# Ch7and8.net
KiCad netlist of a schematic drawn in Altium Designer
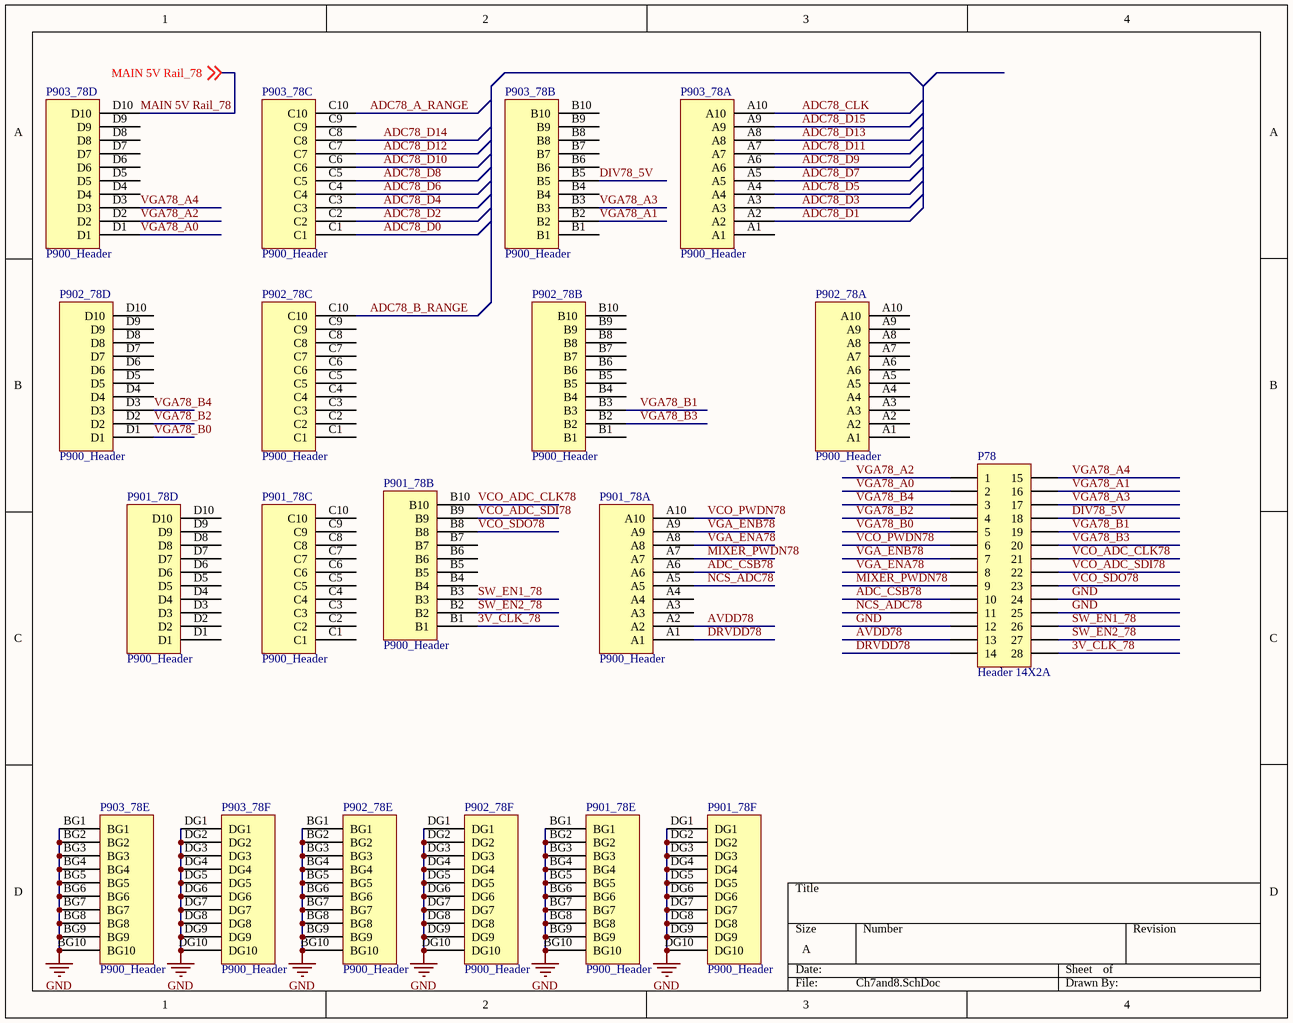
[diagram p0: Ch7and8.SchDoc]

(export (version "E")
  (design (tool "Eeschema 10.0.6"))
  (components
    (comp (ref "P78")
      (value "Header 14X2A")
      (footprint "HDR2X14_CEN")
      (description "Header, 14-Pin, Dual row")
      (fields (field (name "PUBLISHER") "Altium Limited"))
      (libsource (lib "Miscellaneous Connectors") (part "Header 14X2A"))
    )
    (comp (ref "P901_78")
      (value "P900_Header")
      (footprint "P900_header")
      (libsource (lib "") (part "P900_Header_1"))
    )
    (comp (ref "P902_78")
      (value "P900_Header")
      (footprint "P900_header")
      (libsource (lib "MQP_lib") (part "P900_Header"))
    )
    (comp (ref "P903_78")
      (value "P900_Header")
      (footprint "P900_header")
      (libsource (lib "") (part "P900_Header_1"))
    )
  )
  (nets
    (net (code "1") (name "/3V_CLK_78") (class "Default")
      (node (ref "P78") (pin "28") (pinfunction "28_28") (pintype "passive"))
      (node (ref "P901_78") (pin "B1") (pinfunction "B1_B1") (pintype "passive"))
    )
    (net (code "2") (name "/ADC78_A_RANGE") (class "Default")
      (node (ref "P903_78") (pin "C10") (pinfunction "C10_C10") (pintype "passive"))
    )
    (net (code "3") (name "/ADC78_B_RANGE") (class "Default")
      (node (ref "P902_78") (pin "C10") (pinfunction "C10_C10") (pintype "passive"))
    )
    (net (code "4") (name "/ADC78_CLK") (class "Default")
      (node (ref "P903_78") (pin "A10") (pinfunction "A10_A10") (pintype "passive"))
    )
    (net (code "5") (name "/ADC78_D0") (class "Default")
      (node (ref "P903_78") (pin "C1") (pinfunction "C1_C1") (pintype "passive"))
    )
    (net (code "6") (name "/ADC78_D1") (class "Default")
      (node (ref "P903_78") (pin "A2") (pinfunction "A2_A2") (pintype "passive"))
    )
    (net (code "7") (name "/ADC78_D2") (class "Default")
      (node (ref "P903_78") (pin "C2") (pinfunction "C2_C2") (pintype "passive"))
    )
    (net (code "8") (name "/ADC78_D3") (class "Default")
      (node (ref "P903_78") (pin "A3") (pinfunction "A3_A3") (pintype "passive"))
    )
    (net (code "9") (name "/ADC78_D4") (class "Default")
      (node (ref "P903_78") (pin "C3") (pinfunction "C3_C3") (pintype "passive"))
    )
    (net (code "10") (name "/ADC78_D5") (class "Default")
      (node (ref "P903_78") (pin "A4") (pinfunction "A4_A4") (pintype "passive"))
    )
    (net (code "11") (name "/ADC78_D6") (class "Default")
      (node (ref "P903_78") (pin "C4") (pinfunction "C4_C4") (pintype "passive"))
    )
    (net (code "12") (name "/ADC78_D7") (class "Default")
      (node (ref "P903_78") (pin "A5") (pinfunction "A5_A5") (pintype "passive"))
    )
    (net (code "13") (name "/ADC78_D8") (class "Default")
      (node (ref "P903_78") (pin "C5") (pinfunction "C5_C5") (pintype "passive"))
    )
    (net (code "14") (name "/ADC78_D9") (class "Default")
      (node (ref "P903_78") (pin "A6") (pinfunction "A6_A6") (pintype "passive"))
    )
    (net (code "15") (name "/ADC78_D10") (class "Default")
      (node (ref "P903_78") (pin "C6") (pinfunction "C6_C6") (pintype "passive"))
    )
    (net (code "16") (name "/ADC78_D11") (class "Default")
      (node (ref "P903_78") (pin "A7") (pinfunction "A7_A7") (pintype "passive"))
    )
    (net (code "17") (name "/ADC78_D12") (class "Default")
      (node (ref "P903_78") (pin "C7") (pinfunction "C7_C7") (pintype "passive"))
    )
    (net (code "18") (name "/ADC78_D13") (class "Default")
      (node (ref "P903_78") (pin "A8") (pinfunction "A8_A8") (pintype "passive"))
    )
    (net (code "19") (name "/ADC78_D14") (class "Default")
      (node (ref "P903_78") (pin "C8") (pinfunction "C8_C8") (pintype "passive"))
    )
    (net (code "20") (name "/ADC78_D15") (class "Default")
      (node (ref "P903_78") (pin "A9") (pinfunction "A9_A9") (pintype "passive"))
    )
    (net (code "21") (name "/ADC_CSB78") (class "Default")
      (node (ref "P78") (pin "10") (pinfunction "10_10") (pintype "passive"))
      (node (ref "P901_78") (pin "A6") (pinfunction "A6_A6") (pintype "passive"))
    )
    (net (code "22") (name "/AVDD78") (class "Default")
      (node (ref "P78") (pin "13") (pinfunction "13_13") (pintype "passive"))
      (node (ref "P901_78") (pin "A2") (pinfunction "A2_A2") (pintype "passive"))
    )
    (net (code "23") (name "/DIV78_5V") (class "Default")
      (node (ref "P78") (pin "18") (pinfunction "18_18") (pintype "passive"))
      (node (ref "P903_78") (pin "B5") (pinfunction "B5_B5") (pintype "passive"))
    )
    (net (code "24") (name "/DRVDD78") (class "Default")
      (node (ref "P78") (pin "14") (pinfunction "14_14") (pintype "passive"))
      (node (ref "P901_78") (pin "A1") (pinfunction "A1_A1") (pintype "passive"))
    )
    (net (code "25") (name "/MIXER_PWDN78") (class "Default")
      (node (ref "P78") (pin "9") (pinfunction "9_9") (pintype "passive"))
      (node (ref "P901_78") (pin "A7") (pinfunction "A7_A7") (pintype "passive"))
    )
    (net (code "26") (name "/NCS_ADC78") (class "Default")
      (node (ref "P78") (pin "11") (pinfunction "11_11") (pintype "passive"))
      (node (ref "P901_78") (pin "A5") (pinfunction "A5_A5") (pintype "passive"))
    )
    (net (code "27") (name "/SW_EN1_78") (class "Default")
      (node (ref "P78") (pin "26") (pinfunction "26_26") (pintype "passive"))
      (node (ref "P901_78") (pin "B3") (pinfunction "B3_B3") (pintype "passive"))
    )
    (net (code "28") (name "/SW_EN2_78") (class "Default")
      (node (ref "P78") (pin "27") (pinfunction "27_27") (pintype "passive"))
      (node (ref "P901_78") (pin "B2") (pinfunction "B2_B2") (pintype "passive"))
    )
    (net (code "29") (name "/VCO_ADC_CLK78") (class "Default")
      (node (ref "P78") (pin "21") (pinfunction "21_21") (pintype "passive"))
      (node (ref "P901_78") (pin "B10") (pinfunction "B10_B10") (pintype "passive"))
    )
    (net (code "30") (name "/VCO_ADC_SDI78") (class "Default")
      (node (ref "P78") (pin "22") (pinfunction "22_22") (pintype "passive"))
      (node (ref "P901_78") (pin "B9") (pinfunction "B9_B9") (pintype "passive"))
    )
    (net (code "31") (name "/VCO_PWDN78") (class "Default")
      (node (ref "P78") (pin "6") (pinfunction "6_6") (pintype "passive"))
      (node (ref "P901_78") (pin "A10") (pinfunction "A10_A10") (pintype "passive"))
    )
    (net (code "32") (name "/VCO_SDO78") (class "Default")
      (node (ref "P78") (pin "23") (pinfunction "23_23") (pintype "passive"))
      (node (ref "P901_78") (pin "B8") (pinfunction "B8_B8") (pintype "passive"))
    )
    (net (code "33") (name "/VGA78_A0") (class "Default")
      (node (ref "P78") (pin "2") (pinfunction "2_2") (pintype "passive"))
      (node (ref "P903_78") (pin "D1") (pinfunction "D1_D1") (pintype "passive"))
    )
    (net (code "34") (name "/VGA78_A1") (class "Default")
      (node (ref "P78") (pin "16") (pinfunction "16_16") (pintype "passive"))
      (node (ref "P903_78") (pin "B2") (pinfunction "B2_B2") (pintype "passive"))
    )
    (net (code "35") (name "/VGA78_A2") (class "Default")
      (node (ref "P78") (pin "1") (pinfunction "1_1") (pintype "passive"))
      (node (ref "P903_78") (pin "D2") (pinfunction "D2_D2") (pintype "passive"))
    )
    (net (code "36") (name "/VGA78_A3") (class "Default")
      (node (ref "P78") (pin "17") (pinfunction "17_17") (pintype "passive"))
      (node (ref "P903_78") (pin "B3") (pinfunction "B3_B3") (pintype "passive"))
    )
    (net (code "37") (name "/VGA78_A4") (class "Default")
      (node (ref "P78") (pin "15") (pinfunction "15_15") (pintype "passive"))
      (node (ref "P903_78") (pin "D3") (pinfunction "D3_D3") (pintype "passive"))
    )
    (net (code "38") (name "/VGA78_B0") (class "Default")
      (node (ref "P78") (pin "5") (pinfunction "5_5") (pintype "passive"))
      (node (ref "P902_78") (pin "D1") (pinfunction "D1_D1") (pintype "passive"))
    )
    (net (code "39") (name "/VGA78_B1") (class "Default")
      (node (ref "P78") (pin "19") (pinfunction "19_19") (pintype "passive"))
      (node (ref "P902_78") (pin "B3") (pinfunction "B3_B3") (pintype "passive"))
    )
    (net (code "40") (name "/VGA78_B2") (class "Default")
      (node (ref "P78") (pin "4") (pinfunction "4_4") (pintype "passive"))
      (node (ref "P902_78") (pin "D2") (pinfunction "D2_D2") (pintype "passive"))
    )
    (net (code "41") (name "/VGA78_B3") (class "Default")
      (node (ref "P78") (pin "20") (pinfunction "20_20") (pintype "passive"))
      (node (ref "P902_78") (pin "B2") (pinfunction "B2_B2") (pintype "passive"))
    )
    (net (code "42") (name "/VGA78_B4") (class "Default")
      (node (ref "P78") (pin "3") (pinfunction "3_3") (pintype "passive"))
      (node (ref "P902_78") (pin "D3") (pinfunction "D3_D3") (pintype "passive"))
    )
    (net (code "43") (name "/VGA_ENA78") (class "Default")
      (node (ref "P78") (pin "8") (pinfunction "8_8") (pintype "passive"))
      (node (ref "P901_78") (pin "A8") (pinfunction "A8_A8") (pintype "passive"))
    )
    (net (code "44") (name "/VGA_ENB78") (class "Default")
      (node (ref "P78") (pin "7") (pinfunction "7_7") (pintype "passive"))
      (node (ref "P901_78") (pin "A9") (pinfunction "A9_A9") (pintype "passive"))
    )
    (net (code "45") (name "GND") (class "Default")
      (node (ref "P78") (pin "12") (pinfunction "12_12") (pintype "passive"))
      (node (ref "P78") (pin "24") (pinfunction "24_24") (pintype "passive"))
      (node (ref "P78") (pin "25") (pinfunction "25_25") (pintype "passive"))
      (node (ref "P901_78") (pin "BG1") (pinfunction "BG1_BG1") (pintype "passive"))
      (node (ref "P901_78") (pin "BG10") (pinfunction "BG10_BG10") (pintype "passive"))
      (node (ref "P901_78") (pin "BG2") (pinfunction "BG2_BG2") (pintype "passive"))
      (node (ref "P901_78") (pin "BG3") (pinfunction "BG3_BG3") (pintype "passive"))
      (node (ref "P901_78") (pin "BG4") (pinfunction "BG4_BG4") (pintype "passive"))
      (node (ref "P901_78") (pin "BG5") (pinfunction "BG5_BG5") (pintype "passive"))
      (node (ref "P901_78") (pin "BG6") (pinfunction "BG6_BG6") (pintype "passive"))
      (node (ref "P901_78") (pin "BG7") (pinfunction "BG7_BG7") (pintype "passive"))
      (node (ref "P901_78") (pin "BG8") (pinfunction "BG8_BG8") (pintype "passive"))
      (node (ref "P901_78") (pin "BG9") (pinfunction "BG9_BG9") (pintype "passive"))
      (node (ref "P901_78") (pin "DG1") (pinfunction "DG1_DG1") (pintype "passive"))
      (node (ref "P901_78") (pin "DG10") (pinfunction "DG10_DG10") (pintype "passive"))
      (node (ref "P901_78") (pin "DG2") (pinfunction "DG2_DG2") (pintype "passive"))
      (node (ref "P901_78") (pin "DG3") (pinfunction "DG3_DG3") (pintype "passive"))
      (node (ref "P901_78") (pin "DG4") (pinfunction "DG4_DG4") (pintype "passive"))
      (node (ref "P901_78") (pin "DG5") (pinfunction "DG5_DG5") (pintype "passive"))
      (node (ref "P901_78") (pin "DG6") (pinfunction "DG6_DG6") (pintype "passive"))
      (node (ref "P901_78") (pin "DG7") (pinfunction "DG7_DG7") (pintype "passive"))
      (node (ref "P901_78") (pin "DG8") (pinfunction "DG8_DG8") (pintype "passive"))
      (node (ref "P901_78") (pin "DG9") (pinfunction "DG9_DG9") (pintype "passive"))
      (node (ref "P902_78") (pin "BG1") (pinfunction "BG1_BG1") (pintype "passive"))
      (node (ref "P902_78") (pin "BG10") (pinfunction "BG10_BG10") (pintype "passive"))
      (node (ref "P902_78") (pin "BG2") (pinfunction "BG2_BG2") (pintype "passive"))
      (node (ref "P902_78") (pin "BG3") (pinfunction "BG3_BG3") (pintype "passive"))
      (node (ref "P902_78") (pin "BG4") (pinfunction "BG4_BG4") (pintype "passive"))
      (node (ref "P902_78") (pin "BG5") (pinfunction "BG5_BG5") (pintype "passive"))
      (node (ref "P902_78") (pin "BG6") (pinfunction "BG6_BG6") (pintype "passive"))
      (node (ref "P902_78") (pin "BG7") (pinfunction "BG7_BG7") (pintype "passive"))
      (node (ref "P902_78") (pin "BG8") (pinfunction "BG8_BG8") (pintype "passive"))
      (node (ref "P902_78") (pin "BG9") (pinfunction "BG9_BG9") (pintype "passive"))
      (node (ref "P902_78") (pin "DG1") (pinfunction "DG1_DG1") (pintype "passive"))
      (node (ref "P902_78") (pin "DG10") (pinfunction "DG10_DG10") (pintype "passive"))
      (node (ref "P902_78") (pin "DG2") (pinfunction "DG2_DG2") (pintype "passive"))
      (node (ref "P902_78") (pin "DG3") (pinfunction "DG3_DG3") (pintype "passive"))
      (node (ref "P902_78") (pin "DG4") (pinfunction "DG4_DG4") (pintype "passive"))
      (node (ref "P902_78") (pin "DG5") (pinfunction "DG5_DG5") (pintype "passive"))
      (node (ref "P902_78") (pin "DG6") (pinfunction "DG6_DG6") (pintype "passive"))
      (node (ref "P902_78") (pin "DG7") (pinfunction "DG7_DG7") (pintype "passive"))
      (node (ref "P902_78") (pin "DG8") (pinfunction "DG8_DG8") (pintype "passive"))
      (node (ref "P902_78") (pin "DG9") (pinfunction "DG9_DG9") (pintype "passive"))
      (node (ref "P903_78") (pin "BG1") (pinfunction "BG1_BG1") (pintype "passive"))
      (node (ref "P903_78") (pin "BG10") (pinfunction "BG10_BG10") (pintype "passive"))
      (node (ref "P903_78") (pin "BG2") (pinfunction "BG2_BG2") (pintype "passive"))
      (node (ref "P903_78") (pin "BG3") (pinfunction "BG3_BG3") (pintype "passive"))
      (node (ref "P903_78") (pin "BG4") (pinfunction "BG4_BG4") (pintype "passive"))
      (node (ref "P903_78") (pin "BG5") (pinfunction "BG5_BG5") (pintype "passive"))
      (node (ref "P903_78") (pin "BG6") (pinfunction "BG6_BG6") (pintype "passive"))
      (node (ref "P903_78") (pin "BG7") (pinfunction "BG7_BG7") (pintype "passive"))
      (node (ref "P903_78") (pin "BG8") (pinfunction "BG8_BG8") (pintype "passive"))
      (node (ref "P903_78") (pin "BG9") (pinfunction "BG9_BG9") (pintype "passive"))
      (node (ref "P903_78") (pin "DG1") (pinfunction "DG1_DG1") (pintype "passive"))
      (node (ref "P903_78") (pin "DG10") (pinfunction "DG10_DG10") (pintype "passive"))
      (node (ref "P903_78") (pin "DG2") (pinfunction "DG2_DG2") (pintype "passive"))
      (node (ref "P903_78") (pin "DG3") (pinfunction "DG3_DG3") (pintype "passive"))
      (node (ref "P903_78") (pin "DG4") (pinfunction "DG4_DG4") (pintype "passive"))
      (node (ref "P903_78") (pin "DG5") (pinfunction "DG5_DG5") (pintype "passive"))
      (node (ref "P903_78") (pin "DG6") (pinfunction "DG6_DG6") (pintype "passive"))
      (node (ref "P903_78") (pin "DG7") (pinfunction "DG7_DG7") (pintype "passive"))
      (node (ref "P903_78") (pin "DG8") (pinfunction "DG8_DG8") (pintype "passive"))
      (node (ref "P903_78") (pin "DG9") (pinfunction "DG9_DG9") (pintype "passive"))
    )
    (net (code "46") (name "MAIN 5V Rail_78") (class "Default")
      (node (ref "P903_78") (pin "D10") (pinfunction "D10_D10") (pintype "passive"))
    )
    (net (code "47") (name "unconnected-(P901_78-PadA3)") (class "Default")
      (node (ref "P901_78") (pin "A3") (pinfunction "A3_A3") (pintype "passive"))
    )
    (net (code "48") (name "unconnected-(P901_78-PadA4)") (class "Default")
      (node (ref "P901_78") (pin "A4") (pinfunction "A4_A4") (pintype "passive"))
    )
    (net (code "49") (name "unconnected-(P901_78-PadB4)") (class "Default")
      (node (ref "P901_78") (pin "B4") (pinfunction "B4_B4") (pintype "passive"))
    )
    (net (code "50") (name "unconnected-(P901_78-PadB5)") (class "Default")
      (node (ref "P901_78") (pin "B5") (pinfunction "B5_B5") (pintype "passive"))
    )
    (net (code "51") (name "unconnected-(P901_78-PadB6)") (class "Default")
      (node (ref "P901_78") (pin "B6") (pinfunction "B6_B6") (pintype "passive"))
    )
    (net (code "52") (name "unconnected-(P901_78-PadB7)") (class "Default")
      (node (ref "P901_78") (pin "B7") (pinfunction "B7_B7") (pintype "passive"))
    )
    (net (code "53") (name "unconnected-(P901_78-PadC1)") (class "Default")
      (node (ref "P901_78") (pin "C1") (pinfunction "C1_C1") (pintype "passive"))
    )
    (net (code "54") (name "unconnected-(P901_78-PadC2)") (class "Default")
      (node (ref "P901_78") (pin "C2") (pinfunction "C2_C2") (pintype "passive"))
    )
    (net (code "55") (name "unconnected-(P901_78-PadC3)") (class "Default")
      (node (ref "P901_78") (pin "C3") (pinfunction "C3_C3") (pintype "passive"))
    )
    (net (code "56") (name "unconnected-(P901_78-PadC4)") (class "Default")
      (node (ref "P901_78") (pin "C4") (pinfunction "C4_C4") (pintype "passive"))
    )
    (net (code "57") (name "unconnected-(P901_78-PadC5)") (class "Default")
      (node (ref "P901_78") (pin "C5") (pinfunction "C5_C5") (pintype "passive"))
    )
    (net (code "58") (name "unconnected-(P901_78-PadC6)") (class "Default")
      (node (ref "P901_78") (pin "C6") (pinfunction "C6_C6") (pintype "passive"))
    )
    (net (code "59") (name "unconnected-(P901_78-PadC7)") (class "Default")
      (node (ref "P901_78") (pin "C7") (pinfunction "C7_C7") (pintype "passive"))
    )
    (net (code "60") (name "unconnected-(P901_78-PadC8)") (class "Default")
      (node (ref "P901_78") (pin "C8") (pinfunction "C8_C8") (pintype "passive"))
    )
    (net (code "61") (name "unconnected-(P901_78-PadC9)") (class "Default")
      (node (ref "P901_78") (pin "C9") (pinfunction "C9_C9") (pintype "passive"))
    )
    (net (code "62") (name "unconnected-(P901_78-PadC10)") (class "Default")
      (node (ref "P901_78") (pin "C10") (pinfunction "C10_C10") (pintype "passive"))
    )
    (net (code "63") (name "unconnected-(P901_78-PadD1)") (class "Default")
      (node (ref "P901_78") (pin "D1") (pinfunction "D1_D1") (pintype "passive"))
    )
    (net (code "64") (name "unconnected-(P901_78-PadD2)") (class "Default")
      (node (ref "P901_78") (pin "D2") (pinfunction "D2_D2") (pintype "passive"))
    )
    (net (code "65") (name "unconnected-(P901_78-PadD3)") (class "Default")
      (node (ref "P901_78") (pin "D3") (pinfunction "D3_D3") (pintype "passive"))
    )
    (net (code "66") (name "unconnected-(P901_78-PadD4)") (class "Default")
      (node (ref "P901_78") (pin "D4") (pinfunction "D4_D4") (pintype "passive"))
    )
    (net (code "67") (name "unconnected-(P901_78-PadD5)") (class "Default")
      (node (ref "P901_78") (pin "D5") (pinfunction "D5_D5") (pintype "passive"))
    )
    (net (code "68") (name "unconnected-(P901_78-PadD6)") (class "Default")
      (node (ref "P901_78") (pin "D6") (pinfunction "D6_D6") (pintype "passive"))
    )
    (net (code "69") (name "unconnected-(P901_78-PadD7)") (class "Default")
      (node (ref "P901_78") (pin "D7") (pinfunction "D7_D7") (pintype "passive"))
    )
    (net (code "70") (name "unconnected-(P901_78-PadD8)") (class "Default")
      (node (ref "P901_78") (pin "D8") (pinfunction "D8_D8") (pintype "passive"))
    )
    (net (code "71") (name "unconnected-(P901_78-PadD9)") (class "Default")
      (node (ref "P901_78") (pin "D9") (pinfunction "D9_D9") (pintype "passive"))
    )
    (net (code "72") (name "unconnected-(P901_78-PadD10)") (class "Default")
      (node (ref "P901_78") (pin "D10") (pinfunction "D10_D10") (pintype "passive"))
    )
    (net (code "73") (name "unconnected-(P902_78-PadA1)") (class "Default")
      (node (ref "P902_78") (pin "A1") (pinfunction "A1_A1") (pintype "passive"))
    )
    (net (code "74") (name "unconnected-(P902_78-PadA2)") (class "Default")
      (node (ref "P902_78") (pin "A2") (pinfunction "A2_A2") (pintype "passive"))
    )
    (net (code "75") (name "unconnected-(P902_78-PadA3)") (class "Default")
      (node (ref "P902_78") (pin "A3") (pinfunction "A3_A3") (pintype "passive"))
    )
    (net (code "76") (name "unconnected-(P902_78-PadA4)") (class "Default")
      (node (ref "P902_78") (pin "A4") (pinfunction "A4_A4") (pintype "passive"))
    )
    (net (code "77") (name "unconnected-(P902_78-PadA5)") (class "Default")
      (node (ref "P902_78") (pin "A5") (pinfunction "A5_A5") (pintype "passive"))
    )
    (net (code "78") (name "unconnected-(P902_78-PadA6)") (class "Default")
      (node (ref "P902_78") (pin "A6") (pinfunction "A6_A6") (pintype "passive"))
    )
    (net (code "79") (name "unconnected-(P902_78-PadA7)") (class "Default")
      (node (ref "P902_78") (pin "A7") (pinfunction "A7_A7") (pintype "passive"))
    )
    (net (code "80") (name "unconnected-(P902_78-PadA8)") (class "Default")
      (node (ref "P902_78") (pin "A8") (pinfunction "A8_A8") (pintype "passive"))
    )
    (net (code "81") (name "unconnected-(P902_78-PadA9)") (class "Default")
      (node (ref "P902_78") (pin "A9") (pinfunction "A9_A9") (pintype "passive"))
    )
    (net (code "82") (name "unconnected-(P902_78-PadA10)") (class "Default")
      (node (ref "P902_78") (pin "A10") (pinfunction "A10_A10") (pintype "passive"))
    )
    (net (code "83") (name "unconnected-(P902_78-PadB1)") (class "Default")
      (node (ref "P902_78") (pin "B1") (pinfunction "B1_B1") (pintype "passive"))
    )
    (net (code "84") (name "unconnected-(P902_78-PadB4)") (class "Default")
      (node (ref "P902_78") (pin "B4") (pinfunction "B4_B4") (pintype "passive"))
    )
    (net (code "85") (name "unconnected-(P902_78-PadB5)") (class "Default")
      (node (ref "P902_78") (pin "B5") (pinfunction "B5_B5") (pintype "passive"))
    )
    (net (code "86") (name "unconnected-(P902_78-PadB6)") (class "Default")
      (node (ref "P902_78") (pin "B6") (pinfunction "B6_B6") (pintype "passive"))
    )
    (net (code "87") (name "unconnected-(P902_78-PadB7)") (class "Default")
      (node (ref "P902_78") (pin "B7") (pinfunction "B7_B7") (pintype "passive"))
    )
    (net (code "88") (name "unconnected-(P902_78-PadB8)") (class "Default")
      (node (ref "P902_78") (pin "B8") (pinfunction "B8_B8") (pintype "passive"))
    )
    (net (code "89") (name "unconnected-(P902_78-PadB9)") (class "Default")
      (node (ref "P902_78") (pin "B9") (pinfunction "B9_B9") (pintype "passive"))
    )
    (net (code "90") (name "unconnected-(P902_78-PadB10)") (class "Default")
      (node (ref "P902_78") (pin "B10") (pinfunction "B10_B10") (pintype "passive"))
    )
    (net (code "91") (name "unconnected-(P902_78-PadC1)") (class "Default")
      (node (ref "P902_78") (pin "C1") (pinfunction "C1_C1") (pintype "passive"))
    )
    (net (code "92") (name "unconnected-(P902_78-PadC2)") (class "Default")
      (node (ref "P902_78") (pin "C2") (pinfunction "C2_C2") (pintype "passive"))
    )
    (net (code "93") (name "unconnected-(P902_78-PadC3)") (class "Default")
      (node (ref "P902_78") (pin "C3") (pinfunction "C3_C3") (pintype "passive"))
    )
    (net (code "94") (name "unconnected-(P902_78-PadC4)") (class "Default")
      (node (ref "P902_78") (pin "C4") (pinfunction "C4_C4") (pintype "passive"))
    )
    (net (code "95") (name "unconnected-(P902_78-PadC5)") (class "Default")
      (node (ref "P902_78") (pin "C5") (pinfunction "C5_C5") (pintype "passive"))
    )
    (net (code "96") (name "unconnected-(P902_78-PadC6)") (class "Default")
      (node (ref "P902_78") (pin "C6") (pinfunction "C6_C6") (pintype "passive"))
    )
    (net (code "97") (name "unconnected-(P902_78-PadC7)") (class "Default")
      (node (ref "P902_78") (pin "C7") (pinfunction "C7_C7") (pintype "passive"))
    )
    (net (code "98") (name "unconnected-(P902_78-PadC8)") (class "Default")
      (node (ref "P902_78") (pin "C8") (pinfunction "C8_C8") (pintype "passive"))
    )
    (net (code "99") (name "unconnected-(P902_78-PadC9)") (class "Default")
      (node (ref "P902_78") (pin "C9") (pinfunction "C9_C9") (pintype "passive"))
    )
    (net (code "100") (name "unconnected-(P902_78-PadD4)") (class "Default")
      (node (ref "P902_78") (pin "D4") (pinfunction "D4_D4") (pintype "passive"))
    )
    (net (code "101") (name "unconnected-(P902_78-PadD5)") (class "Default")
      (node (ref "P902_78") (pin "D5") (pinfunction "D5_D5") (pintype "passive"))
    )
    (net (code "102") (name "unconnected-(P902_78-PadD6)") (class "Default")
      (node (ref "P902_78") (pin "D6") (pinfunction "D6_D6") (pintype "passive"))
    )
    (net (code "103") (name "unconnected-(P902_78-PadD7)") (class "Default")
      (node (ref "P902_78") (pin "D7") (pinfunction "D7_D7") (pintype "passive"))
    )
    (net (code "104") (name "unconnected-(P902_78-PadD8)") (class "Default")
      (node (ref "P902_78") (pin "D8") (pinfunction "D8_D8") (pintype "passive"))
    )
    (net (code "105") (name "unconnected-(P902_78-PadD9)") (class "Default")
      (node (ref "P902_78") (pin "D9") (pinfunction "D9_D9") (pintype "passive"))
    )
    (net (code "106") (name "unconnected-(P902_78-PadD10)") (class "Default")
      (node (ref "P902_78") (pin "D10") (pinfunction "D10_D10") (pintype "passive"))
    )
    (net (code "107") (name "unconnected-(P903_78-PadA1)") (class "Default")
      (node (ref "P903_78") (pin "A1") (pinfunction "A1_A1") (pintype "passive"))
    )
    (net (code "108") (name "unconnected-(P903_78-PadB1)") (class "Default")
      (node (ref "P903_78") (pin "B1") (pinfunction "B1_B1") (pintype "passive"))
    )
    (net (code "109") (name "unconnected-(P903_78-PadB4)") (class "Default")
      (node (ref "P903_78") (pin "B4") (pinfunction "B4_B4") (pintype "passive"))
    )
    (net (code "110") (name "unconnected-(P903_78-PadB6)") (class "Default")
      (node (ref "P903_78") (pin "B6") (pinfunction "B6_B6") (pintype "passive"))
    )
    (net (code "111") (name "unconnected-(P903_78-PadB7)") (class "Default")
      (node (ref "P903_78") (pin "B7") (pinfunction "B7_B7") (pintype "passive"))
    )
    (net (code "112") (name "unconnected-(P903_78-PadB8)") (class "Default")
      (node (ref "P903_78") (pin "B8") (pinfunction "B8_B8") (pintype "passive"))
    )
    (net (code "113") (name "unconnected-(P903_78-PadB9)") (class "Default")
      (node (ref "P903_78") (pin "B9") (pinfunction "B9_B9") (pintype "passive"))
    )
    (net (code "114") (name "unconnected-(P903_78-PadB10)") (class "Default")
      (node (ref "P903_78") (pin "B10") (pinfunction "B10_B10") (pintype "passive"))
    )
    (net (code "115") (name "unconnected-(P903_78-PadC9)") (class "Default")
      (node (ref "P903_78") (pin "C9") (pinfunction "C9_C9") (pintype "passive"))
    )
    (net (code "116") (name "unconnected-(P903_78-PadD4)") (class "Default")
      (node (ref "P903_78") (pin "D4") (pinfunction "D4_D4") (pintype "passive"))
    )
    (net (code "117") (name "unconnected-(P903_78-PadD5)") (class "Default")
      (node (ref "P903_78") (pin "D5") (pinfunction "D5_D5") (pintype "passive"))
    )
    (net (code "118") (name "unconnected-(P903_78-PadD6)") (class "Default")
      (node (ref "P903_78") (pin "D6") (pinfunction "D6_D6") (pintype "passive"))
    )
    (net (code "119") (name "unconnected-(P903_78-PadD7)") (class "Default")
      (node (ref "P903_78") (pin "D7") (pinfunction "D7_D7") (pintype "passive"))
    )
    (net (code "120") (name "unconnected-(P903_78-PadD8)") (class "Default")
      (node (ref "P903_78") (pin "D8") (pinfunction "D8_D8") (pintype "passive"))
    )
    (net (code "121") (name "unconnected-(P903_78-PadD9)") (class "Default")
      (node (ref "P903_78") (pin "D9") (pinfunction "D9_D9") (pintype "passive"))
    )
  )
)
